# OpenScale.net
KiCad netlist of a schematic drawn in EAGLE
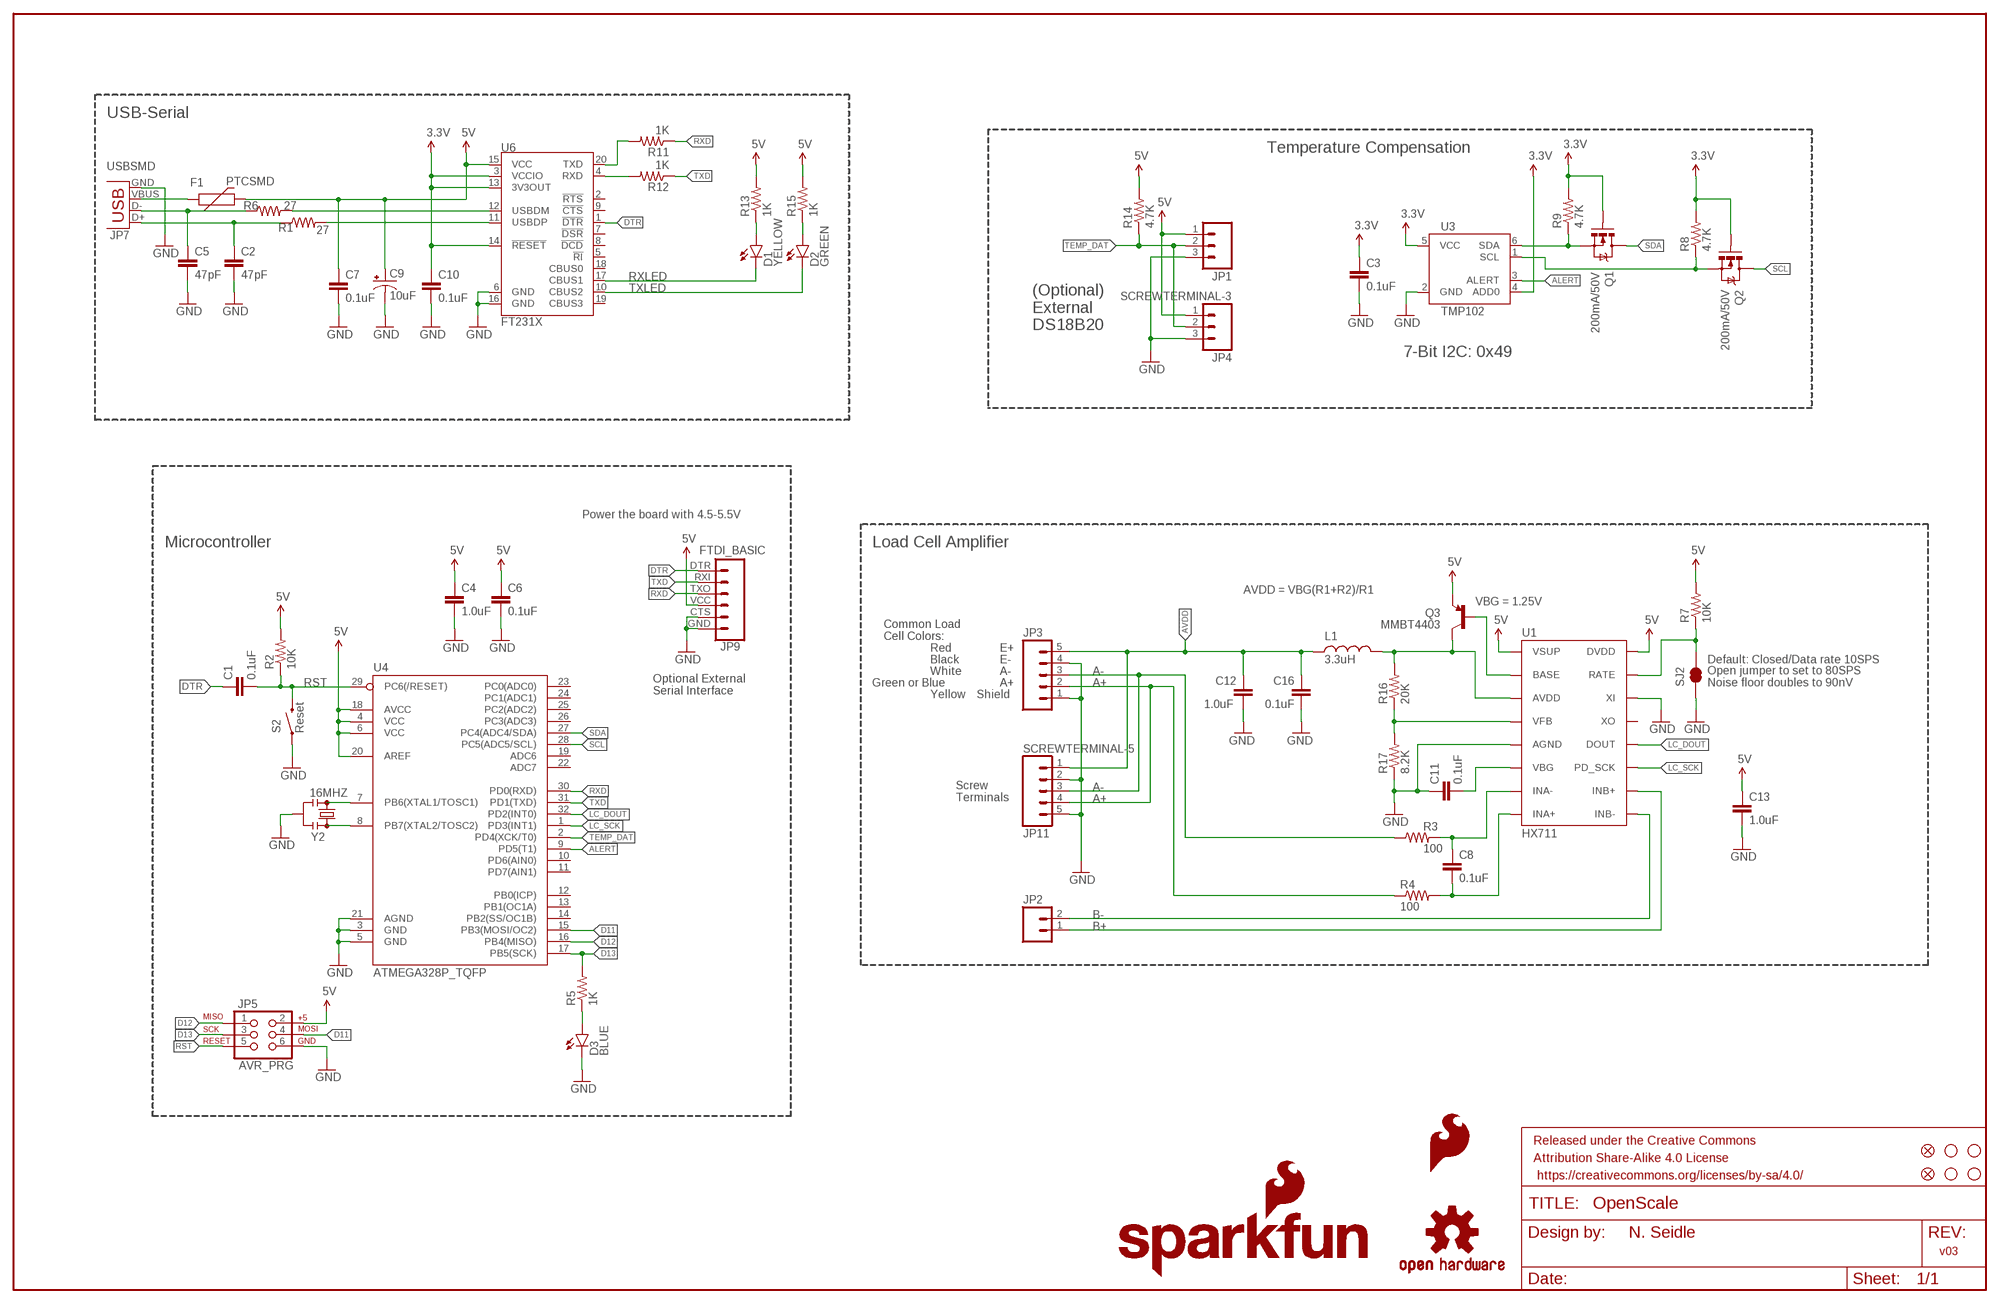
[diagram p0: schematic, sheet 1]

(export (version "E")
  (design (tool "Eeschema 10.0.6"))
  (components
    (comp (ref "C1")
      (value "0.1uF")
      (footprint "eagle-import:0603-CAP")
      (libsource (lib "eagle-import") (part "0.1UF-25V(+80/-20%)(0603)"))
    )
    (comp (ref "C2")
      (value "47pF")
      (footprint "eagle-import:0603-CAP")
      (libsource (lib "eagle-import") (part "47PF-50V-5%(0603)"))
    )
    (comp (ref "C3")
      (value "0.1uF")
      (footprint "eagle-import:0603-CAP")
      (libsource (lib "eagle-import") (part "0.1UF-25V(+80/-20%)(0603)"))
    )
    (comp (ref "C4")
      (value "1.0uF")
      (footprint "eagle-import:0603-CAP")
      (libsource (lib "eagle-import") (part "1.0UF-16V-10%(0603)"))
    )
    (comp (ref "C5")
      (value "47pF")
      (footprint "eagle-import:0603-CAP")
      (libsource (lib "eagle-import") (part "47PF-50V-5%(0603)"))
    )
    (comp (ref "C6")
      (value "0.1uF")
      (footprint "eagle-import:0603-CAP")
      (libsource (lib "eagle-import") (part "0.1UF-25V(+80/-20%)(0603)"))
    )
    (comp (ref "C7")
      (value "0.1uF")
      (footprint "eagle-import:0603-CAP")
      (libsource (lib "eagle-import") (part "0.1UF-25V(+80/-20%)(0603)"))
    )
    (comp (ref "C8")
      (value "0.1uF")
      (footprint "eagle-import:0603-CAP")
      (libsource (lib "eagle-import") (part "0.1UF-25V(+80/-20%)(0603)"))
    )
    (comp (ref "C9")
      (value "10uF")
      (footprint "eagle-import:EIA3216")
      (libsource (lib "eagle-import") (part "10UF-16V-10%(TANT)"))
    )
    (comp (ref "C10")
      (value "0.1uF")
      (footprint "eagle-import:0603-CAP")
      (libsource (lib "eagle-import") (part "0.1UF-25V(+80/-20%)(0603)"))
    )
    (comp (ref "C11")
      (value "0.1uF")
      (footprint "eagle-import:0603-CAP")
      (libsource (lib "eagle-import") (part "0.1UF-25V(+80/-20%)(0603)"))
    )
    (comp (ref "C12")
      (value "1.0uF")
      (footprint "eagle-import:0603-CAP")
      (libsource (lib "eagle-import") (part "1.0UF-16V-10%(0603)"))
    )
    (comp (ref "C13")
      (value "1.0uF")
      (footprint "eagle-import:0603-CAP")
      (libsource (lib "eagle-import") (part "1.0UF-16V-10%(0603)"))
    )
    (comp (ref "C16")
      (value "0.1uF")
      (footprint "eagle-import:0603-CAP")
      (libsource (lib "eagle-import") (part "0.1UF-25V(+80/-20%)(0603)"))
    )
    (comp (ref "D1")
      (value "YELLOW")
      (footprint "eagle-import:LED-1206")
      (libsource (lib "eagle-import") (part "LED-YELLOWLARGE"))
    )
    (comp (ref "D2")
      (value "GREEN")
      (footprint "eagle-import:LED-1206")
      (libsource (lib "eagle-import") (part "LED-GREENLARGE"))
    )
    (comp (ref "D3")
      (value "BLUE")
      (footprint "eagle-import:LED-1206")
      (libsource (lib "eagle-import") (part "LED-BLUE1206"))
    )
    (comp (ref "F1")
      (value "PTCSMD")
      (footprint "eagle-import:PTC-1206")
      (libsource (lib "eagle-import") (part "PTCSMD"))
    )
    (comp (ref "FID1")
      (value "FIDUCIAL1X2")
      (footprint "eagle-import:FIDUCIAL-1X2")
      (libsource (lib "eagle-import") (part "FIDUCIAL1X2"))
    )
    (comp (ref "FID2")
      (value "FIDUCIAL1X2")
      (footprint "eagle-import:FIDUCIAL-1X2")
      (libsource (lib "eagle-import") (part "FIDUCIAL1X2"))
    )
    (comp (ref "FRAME1")
      (value "FRAME-LEDGER")
      (footprint "eagle-import:CREATIVE_COMMONS")
      (fields (field (name "DESIGNER") "N. Seidle") (field (name "VERSION") "v02"))
      (libsource (lib "eagle-import") (part "FRAME-LEDGER"))
    )
    (comp (ref "JP1")
      (value "M031X03_NO_SILK")
      (footprint "eagle-import:1X03_NO_SILK")
      (libsource (lib "eagle-import") (part "M031X03_NO_SILK"))
    )
    (comp (ref "JP2")
      (value "M02PTH")
      (footprint "eagle-import:1X02")
      (libsource (lib "eagle-import") (part "M02PTH"))
    )
    (comp (ref "JP3")
      (value "M05NO_SILK")
      (footprint "eagle-import:1X05_NO_SILK")
      (libsource (lib "eagle-import") (part "M05NO_SILK"))
    )
    (comp (ref "JP4")
      (value "SCREWTERMINAL-3")
      (footprint "eagle-import:SCREWTERMINAL-3.5MM-3_LOCK.007S")
      (libsource (lib "eagle-import") (part "M03SCREW_LOCK"))
    )
    (comp (ref "JP5")
      (value "AVR_PRG")
      (footprint "eagle-import:2X3")
      (libsource (lib "eagle-import") (part "AVR_SPI_PRG_6PTH"))
    )
    (comp (ref "JP7")
      (value "USBSMD")
      (footprint "eagle-import:USB-MINIB")
      (libsource (lib "eagle-import") (part "USBSMD"))
    )
    (comp (ref "JP9")
      (value "FTDI_BASIC")
      (footprint "eagle-import:FTDI_BASIC")
      (libsource (lib "eagle-import") (part "FTDI_BASICPTH"))
    )
    (comp (ref "JP11")
      (value "SCREWTERMINAL-5")
      (footprint "eagle-import:SCREWTERMINAL-3.5MM-5")
      (libsource (lib "eagle-import") (part "M05SCREW"))
    )
    (comp (ref "L1")
      (value "3.3uH")
      (footprint "eagle-import:0805")
      (libsource (lib "eagle-import") (part "INDUCTOR0805"))
    )
    (comp (ref "LOGO1")
      (value "SFE_LOGO_NAME_FLAME.1_INCH")
      (footprint "eagle-import:SFE_LOGO_NAME_FLAME_.1")
      (libsource (lib "eagle-import") (part "SFE_LOGO_NAME_FLAME.1_INCH"))
    )
    (comp (ref "LOGO2")
      (value "OSHW-LOGOS")
      (footprint "eagle-import:OSHW-LOGO-S")
      (libsource (lib "eagle-import") (part "OSHW-LOGOS"))
    )
    (comp (ref "LOGO3")
      (value "SFE_LOGO_FLAME.1_STOP")
      (footprint "eagle-import:SFE_LOGO_FLAME_STOP_.1")
      (libsource (lib "eagle-import") (part "SFE_LOGO_FLAME.1_STOP"))
    )
    (comp (ref "LOGO4")
      (value "SFE_LOGO_NAME_FLAME.1_INCH")
      (footprint "eagle-import:SFE_LOGO_NAME_FLAME_.1")
      (libsource (lib "eagle-import") (part "SFE_LOGO_NAME_FLAME.1_INCH"))
    )
    (comp (ref "Q1")
      (value "200mA/50V")
      (footprint "eagle-import:SOT23-3")
      (libsource (lib "eagle-import") (part "MOSFET-NCHANNELBSS138"))
    )
    (comp (ref "Q2")
      (value "200mA/50V")
      (footprint "eagle-import:SOT23-3")
      (libsource (lib "eagle-import") (part "MOSFET-NCHANNELBSS138"))
    )
    (comp (ref "Q3")
      (value "MMBT4403")
      (footprint "eagle-import:SOT23-3")
      (libsource (lib "eagle-import") (part "TRANSISTOR_PNPMMBT4403"))
    )
    (comp (ref "R1")
      (value "27")
      (footprint "eagle-import:0603")
      (libsource (lib "eagle-import") (part "27OHM1/10W1%(0603)"))
    )
    (comp (ref "R2")
      (value "10K")
      (footprint "eagle-import:0603-RES")
      (libsource (lib "eagle-import") (part "10KOHM-1/10W-1%(0603)0603"))
    )
    (comp (ref "R3")
      (value "100")
      (footprint "eagle-import:0603-RES")
      (libsource (lib "eagle-import") (part "100OHM-1/10W-1%(0603)"))
    )
    (comp (ref "R4")
      (value "100")
      (footprint "eagle-import:0603-RES")
      (libsource (lib "eagle-import") (part "100OHM-1/10W-1%(0603)"))
    )
    (comp (ref "R5")
      (value "1K")
      (footprint "eagle-import:0603-RES")
      (libsource (lib "eagle-import") (part "1KOHM-1/10W-1%(0603)"))
    )
    (comp (ref "R6")
      (value "27")
      (footprint "eagle-import:0603")
      (libsource (lib "eagle-import") (part "27OHM1/10W1%(0603)"))
    )
    (comp (ref "R7")
      (value "10K")
      (footprint "eagle-import:0603-RES")
      (libsource (lib "eagle-import") (part "10KOHM-1/10W-1%(0603)0603"))
    )
    (comp (ref "R8")
      (value "4.7K")
      (footprint "eagle-import:0603-RES")
      (libsource (lib "eagle-import") (part "4.7KOHM-1/10W-1%(0603)"))
    )
    (comp (ref "R9")
      (value "4.7K")
      (footprint "eagle-import:0603-RES")
      (libsource (lib "eagle-import") (part "4.7KOHM-1/10W-1%(0603)"))
    )
    (comp (ref "R11")
      (value "1K")
      (footprint "eagle-import:0603-RES")
      (libsource (lib "eagle-import") (part "1KOHM-1/10W-1%(0603)"))
    )
    (comp (ref "R12")
      (value "1K")
      (footprint "eagle-import:0603-RES")
      (libsource (lib "eagle-import") (part "1KOHM-1/10W-1%(0603)"))
    )
    (comp (ref "R13")
      (value "1K")
      (footprint "eagle-import:0603-RES")
      (libsource (lib "eagle-import") (part "1KOHM-1/10W-1%(0603)"))
    )
    (comp (ref "R14")
      (value "4.7K")
      (footprint "eagle-import:0603-RES")
      (libsource (lib "eagle-import") (part "4.7KOHM-1/10W-1%(0603)"))
    )
    (comp (ref "R15")
      (value "1K")
      (footprint "eagle-import:0603-RES")
      (libsource (lib "eagle-import") (part "1KOHM-1/10W-1%(0603)"))
    )
    (comp (ref "R16")
      (value "20K")
      (footprint "eagle-import:0603-RES")
      (libsource (lib "eagle-import") (part "20KOHM1/10W1%(0603)"))
    )
    (comp (ref "R17")
      (value "8.2K")
      (footprint "eagle-import:0603-RES")
      (libsource (lib "eagle-import") (part "8.2KOHM-1/10W-5%(0603)"))
    )
    (comp (ref "S2")
      (value "Reset")
      (footprint "eagle-import:TACTILE-SWITCH-1101NE")
      (libsource (lib "eagle-import") (part "SWITCH-MOMENTARY-2SMD-1101NE"))
    )
    (comp (ref "SJ2")
      (value "JUMPER-PAD-2-NC_BY_TRACE")
      (footprint "eagle-import:PAD-JUMPER-2-NC_BY_TRACE_YES_SILK")
      (libsource (lib "eagle-import") (part "JUMPER-PAD-2-NC_BY_TRACE"))
    )
    (comp (ref "STANDOFF1")
      (value "STAND-OFF")
      (footprint "eagle-import:STAND-OFF")
      (libsource (lib "eagle-import") (part "STAND-OFF"))
    )
    (comp (ref "STANDOFF2")
      (value "STAND-OFF")
      (footprint "eagle-import:STAND-OFF")
      (libsource (lib "eagle-import") (part "STAND-OFF"))
    )
    (comp (ref "STANDOFF3")
      (value "STAND-OFF")
      (footprint "eagle-import:STAND-OFF")
      (libsource (lib "eagle-import") (part "STAND-OFF"))
    )
    (comp (ref "STANDOFF4")
      (value "STAND-OFF")
      (footprint "eagle-import:STAND-OFF")
      (libsource (lib "eagle-import") (part "STAND-OFF"))
    )
    (comp (ref "U1")
      (value "HX711")
      (footprint "eagle-import:SO16")
      (libsource (lib "eagle-import") (part "HX711HX711"))
    )
    (comp (ref "U3")
      (value "TMP102")
      (footprint "eagle-import:SOT563")
      (libsource (lib "eagle-import") (part "TMP102"))
    )
    (comp (ref "U4")
      (value "ATMEGA328P_TQFP")
      (footprint "eagle-import:TQFP32-08")
      (libsource (lib "eagle-import") (part "ATMEGA328P_TQFP"))
    )
    (comp (ref "U6")
      (value "FT231X")
      (footprint "eagle-import:SSOP20_L")
      (libsource (lib "eagle-import") (part "FT231XS"))
    )
    (comp (ref "Y2")
      (value "16MHZ")
      (footprint "eagle-import:RESONATOR-SMD")
      (libsource (lib "eagle-import") (part "RESONATOR16MHZ"))
    )
  )
  (nets
    (net (code "1") (name "/A+") (class "Default")
      (node (ref "JP11") (pin "4") (pinfunction "4_4") (pintype "passive"))
      (node (ref "JP3") (pin "2") (pinfunction "2_2") (pintype "passive"))
      (node (ref "R4") (pin "1") (pinfunction "1_1") (pintype "passive"))
    )
    (net (code "2") (name "/A-") (class "Default")
      (node (ref "JP11") (pin "3") (pinfunction "3_3") (pintype "passive"))
      (node (ref "JP3") (pin "3") (pinfunction "3_3") (pintype "passive"))
      (node (ref "R3") (pin "1") (pinfunction "1_1") (pintype "passive"))
    )
    (net (code "3") (name "/B+") (class "Default")
      (node (ref "JP2") (pin "1") (pinfunction "1_1") (pintype "passive"))
      (node (ref "U1") (pin "10") (pinfunction "INB+_10") (pintype "bidirectional"))
    )
    (net (code "4") (name "/B-") (class "Default")
      (node (ref "JP2") (pin "2") (pinfunction "2_2") (pintype "passive"))
      (node (ref "U1") (pin "9") (pinfunction "INB-_9") (pintype "bidirectional"))
    )
    (net (code "5") (name "/RXLED") (class "Default")
      (node (ref "D1") (pin "C") (pinfunction "C_C") (pintype "passive"))
      (node (ref "U6") (pin "17") (pinfunction "CBUS1_17") (pintype "bidirectional"))
    )
    (net (code "6") (name "/TXLED") (class "Default")
      (node (ref "D2") (pin "C") (pinfunction "C_C") (pintype "passive"))
      (node (ref "U6") (pin "10") (pinfunction "CBUS2_10") (pintype "bidirectional"))
    )
    (net (code "7") (name "3.3V") (class "Default")
      (node (ref "C10") (pin "1") (pinfunction "1_1") (pintype "passive"))
      (node (ref "C3") (pin "1") (pinfunction "1_1") (pintype "passive"))
      (node (ref "Q1") (pin "1") (pinfunction "G_1") (pintype "passive"))
      (node (ref "Q2") (pin "1") (pinfunction "G_1") (pintype "passive"))
      (node (ref "R8") (pin "2") (pinfunction "2_2") (pintype "passive"))
      (node (ref "R9") (pin "2") (pinfunction "2_2") (pintype "passive"))
      (node (ref "U3") (pin "4") (pinfunction "ADD0_4") (pintype "bidirectional"))
      (node (ref "U3") (pin "5") (pinfunction "VCC_5") (pintype "bidirectional"))
      (node (ref "U6") (pin "13") (pinfunction "3V3OUT_13") (pintype "bidirectional"))
      (node (ref "U6") (pin "14") (pinfunction "~{RESET}_14") (pintype "bidirectional"))
      (node (ref "U6") (pin "3") (pinfunction "VCCIO_3") (pintype "bidirectional"))
    )
    (net (code "8") (name "5V") (class "Default")
      (node (ref "C13") (pin "1") (pinfunction "1_1") (pintype "passive"))
      (node (ref "C4") (pin "1") (pinfunction "1_1") (pintype "passive"))
      (node (ref "C6") (pin "1") (pinfunction "1_1") (pintype "passive"))
      (node (ref "C7") (pin "1") (pinfunction "1_1") (pintype "passive"))
      (node (ref "C9") (pin "A") (pinfunction "+_A") (pintype "passive"))
      (node (ref "F1") (pin "2") (pinfunction "2_2") (pintype "bidirectional"))
      (node (ref "JP1") (pin "1") (pinfunction "1_1") (pintype "passive"))
      (node (ref "JP4") (pin "1") (pinfunction "1_1") (pintype "passive"))
      (node (ref "JP5") (pin "2") (pinfunction "2_2") (pintype "passive"))
      (node (ref "JP9") (pin "VCC") (pinfunction "4_VCC") (pintype "passive"))
      (node (ref "Q3") (pin "2") (pinfunction "E_2") (pintype "passive"))
      (node (ref "R13") (pin "2") (pinfunction "2_2") (pintype "passive"))
      (node (ref "R14") (pin "2") (pinfunction "2_2") (pintype "passive"))
      (node (ref "R15") (pin "2") (pinfunction "2_2") (pintype "passive"))
      (node (ref "R2") (pin "2") (pinfunction "2_2") (pintype "passive"))
      (node (ref "R7") (pin "2") (pinfunction "2_2") (pintype "passive"))
      (node (ref "U1") (pin "1") (pinfunction "VSUP_1") (pintype "bidirectional"))
      (node (ref "U1") (pin "16") (pinfunction "DVDD_16") (pintype "bidirectional"))
      (node (ref "U4") (pin "18") (pinfunction "AVCC_18") (pintype "bidirectional"))
      (node (ref "U4") (pin "20") (pinfunction "AREF_20") (pintype "bidirectional"))
      (node (ref "U4") (pin "4") (pinfunction "VCC_4") (pintype "bidirectional"))
      (node (ref "U4") (pin "6") (pinfunction "VCC_6") (pintype "bidirectional"))
      (node (ref "U6") (pin "15") (pinfunction "VCC_15") (pintype "bidirectional"))
    )
    (net (code "9") (name "ALERT") (class "Default")
      (node (ref "U3") (pin "3") (pinfunction "ALERT_3") (pintype "bidirectional"))
      (node (ref "U4") (pin "9") (pinfunction "PD5(T1)_9") (pintype "bidirectional"))
    )
    (net (code "10") (name "AVDD") (class "Default")
      (node (ref "C12") (pin "2") (pinfunction "2_2") (pintype "passive"))
      (node (ref "C16") (pin "1") (pinfunction "1_1") (pintype "passive"))
      (node (ref "JP11") (pin "1") (pinfunction "1_1") (pintype "passive"))
      (node (ref "JP3") (pin "5") (pinfunction "5_5") (pintype "passive"))
      (node (ref "L1") (pin "1") (pinfunction "1_1") (pintype "passive"))
    )
    (net (code "11") (name "D11") (class "Default")
      (node (ref "JP5") (pin "4") (pinfunction "4_4") (pintype "passive"))
      (node (ref "U4") (pin "15") (pinfunction "PB3(MOSI/OC2)_15") (pintype "bidirectional"))
    )
    (net (code "12") (name "D12") (class "Default")
      (node (ref "JP5") (pin "1") (pinfunction "1_1") (pintype "passive"))
      (node (ref "U4") (pin "16") (pinfunction "PB4(MISO)_16") (pintype "bidirectional"))
    )
    (net (code "13") (name "D13") (class "Default")
      (node (ref "JP5") (pin "3") (pinfunction "3_3") (pintype "passive"))
      (node (ref "R5") (pin "2") (pinfunction "2_2") (pintype "passive"))
      (node (ref "U4") (pin "17") (pinfunction "PB5(SCK)_17") (pintype "bidirectional"))
    )
    (net (code "14") (name "DTR") (class "Default")
      (node (ref "C1") (pin "1") (pinfunction "1_1") (pintype "passive"))
      (node (ref "JP9") (pin "DTR") (pinfunction "1_DTR") (pintype "passive"))
      (node (ref "U6") (pin "1") (pinfunction "~{DTR}_1") (pintype "bidirectional"))
    )
    (net (code "15") (name "GND") (class "Default")
      (node (ref "C10") (pin "2") (pinfunction "2_2") (pintype "passive"))
      (node (ref "C11") (pin "1") (pinfunction "1_1") (pintype "passive"))
      (node (ref "C12") (pin "1") (pinfunction "1_1") (pintype "passive"))
      (node (ref "C13") (pin "2") (pinfunction "2_2") (pintype "passive"))
      (node (ref "C16") (pin "2") (pinfunction "2_2") (pintype "passive"))
      (node (ref "C2") (pin "2") (pinfunction "2_2") (pintype "passive"))
      (node (ref "C3") (pin "2") (pinfunction "2_2") (pintype "passive"))
      (node (ref "C4") (pin "2") (pinfunction "2_2") (pintype "passive"))
      (node (ref "C5") (pin "2") (pinfunction "2_2") (pintype "passive"))
      (node (ref "C6") (pin "2") (pinfunction "2_2") (pintype "passive"))
      (node (ref "C7") (pin "2") (pinfunction "2_2") (pintype "passive"))
      (node (ref "C9") (pin "C") (pinfunction "-_C") (pintype "passive"))
      (node (ref "D3") (pin "C") (pinfunction "C_C") (pintype "passive"))
      (node (ref "JP1") (pin "3") (pinfunction "3_3") (pintype "passive"))
      (node (ref "JP11") (pin "2") (pinfunction "2_2") (pintype "passive"))
      (node (ref "JP11") (pin "5") (pinfunction "5_5") (pintype "passive"))
      (node (ref "JP3") (pin "1") (pinfunction "1_1") (pintype "passive"))
      (node (ref "JP3") (pin "4") (pinfunction "4_4") (pintype "passive"))
      (node (ref "JP4") (pin "3") (pinfunction "3_3") (pintype "passive"))
      (node (ref "JP5") (pin "6") (pinfunction "6_6") (pintype "passive"))
      (node (ref "JP7") (pin "GND") (pinfunction "GND_GND") (pintype "bidirectional"))
      (node (ref "JP9") (pin "CTS") (pinfunction "5_CTS") (pintype "passive"))
      (node (ref "JP9") (pin "GND") (pinfunction "6_GND") (pintype "passive"))
      (node (ref "R17") (pin "1") (pinfunction "1_1") (pintype "passive"))
      (node (ref "S2") (pin "1") (pinfunction "1_1") (pintype "passive"))
      (node (ref "SJ2") (pin "1") (pinfunction "1_1") (pintype "passive"))
      (node (ref "U1") (pin "14") (pinfunction "XI_14") (pintype "bidirectional"))
      (node (ref "U1") (pin "5") (pinfunction "AGND_5") (pintype "bidirectional"))
      (node (ref "U3") (pin "2") (pinfunction "GND_2") (pintype "bidirectional"))
      (node (ref "U4") (pin "21") (pinfunction "AGND_21") (pintype "bidirectional"))
      (node (ref "U4") (pin "3") (pinfunction "GND_3") (pintype "bidirectional"))
      (node (ref "U4") (pin "5") (pinfunction "GND_5") (pintype "bidirectional"))
      (node (ref "U6") (pin "16") (pinfunction "GND_16") (pintype "bidirectional"))
      (node (ref "U6") (pin "6") (pinfunction "GND_6") (pintype "bidirectional"))
      (node (ref "Y2") (pin "2") (pinfunction "2_2") (pintype "passive"))
    )
    (net (code "16") (name "LC_DOUT") (class "Default")
      (node (ref "U1") (pin "12") (pinfunction "DOUT_12") (pintype "bidirectional"))
      (node (ref "U4") (pin "32") (pinfunction "PD2(INT0)_32") (pintype "bidirectional"))
    )
    (net (code "17") (name "LC_SCK") (class "Default")
      (node (ref "U1") (pin "11") (pinfunction "PD_SCK_11") (pintype "bidirectional"))
      (node (ref "U4") (pin "1") (pinfunction "PD3(INT1)_1") (pintype "bidirectional"))
    )
    (net (code "18") (name "Net-(C2-Pad1)") (class "Default")
      (node (ref "C2") (pin "1") (pinfunction "1_1") (pintype "passive"))
      (node (ref "JP7") (pin "D+") (pinfunction "D+_D+") (pintype "bidirectional"))
      (node (ref "R1") (pin "1") (pinfunction "1_1") (pintype "passive"))
    )
    (net (code "19") (name "Net-(C5-Pad1)") (class "Default")
      (node (ref "C5") (pin "1") (pinfunction "1_1") (pintype "passive"))
      (node (ref "JP7") (pin "D-") (pinfunction "D-_D-") (pintype "bidirectional"))
      (node (ref "R6") (pin "1") (pinfunction "1_1") (pintype "passive"))
    )
    (net (code "20") (name "Net-(D1-PadA)") (class "Default")
      (node (ref "D1") (pin "A") (pinfunction "A_A") (pintype "passive"))
      (node (ref "R13") (pin "1") (pinfunction "1_1") (pintype "passive"))
    )
    (net (code "21") (name "Net-(D2-PadA)") (class "Default")
      (node (ref "D2") (pin "A") (pinfunction "A_A") (pintype "passive"))
      (node (ref "R15") (pin "1") (pinfunction "1_1") (pintype "passive"))
    )
    (net (code "22") (name "Net-(D3-PadA)") (class "Default")
      (node (ref "D3") (pin "A") (pinfunction "A_A") (pintype "passive"))
      (node (ref "R5") (pin "1") (pinfunction "1_1") (pintype "passive"))
    )
    (net (code "23") (name "Net-(F1-Pad1)") (class "Default")
      (node (ref "F1") (pin "1") (pinfunction "1_1") (pintype "bidirectional"))
      (node (ref "JP7") (pin "VBUS") (pinfunction "VBUS_VBUS") (pintype "bidirectional"))
    )
    (net (code "24") (name "Net-(Q1-S)") (class "Default")
      (node (ref "Q1") (pin "2") (pinfunction "S_2") (pintype "passive"))
      (node (ref "R9") (pin "1") (pinfunction "1_1") (pintype "passive"))
      (node (ref "U3") (pin "6") (pinfunction "SDA_6") (pintype "bidirectional"))
    )
    (net (code "25") (name "Net-(Q2-S)") (class "Default")
      (node (ref "Q2") (pin "2") (pinfunction "S_2") (pintype "passive"))
      (node (ref "R8") (pin "1") (pinfunction "1_1") (pintype "passive"))
      (node (ref "U3") (pin "1") (pinfunction "SCL_1") (pintype "bidirectional"))
    )
    (net (code "26") (name "Net-(Q3-B)") (class "Default")
      (node (ref "Q3") (pin "1") (pinfunction "B_1") (pintype "passive"))
      (node (ref "U1") (pin "2") (pinfunction "BASE_2") (pintype "bidirectional"))
    )
    (net (code "27") (name "Net-(Q3-C)") (class "Default")
      (node (ref "L1") (pin "2") (pinfunction "2_2") (pintype "passive"))
      (node (ref "Q3") (pin "3") (pinfunction "C_3") (pintype "passive"))
      (node (ref "R16") (pin "2") (pinfunction "2_2") (pintype "passive"))
      (node (ref "U1") (pin "3") (pinfunction "AVDD_3") (pintype "bidirectional"))
    )
    (net (code "28") (name "Net-(U1-INA+)") (class "Default")
      (node (ref "C8") (pin "2") (pinfunction "2_2") (pintype "passive"))
      (node (ref "R4") (pin "2") (pinfunction "2_2") (pintype "passive"))
      (node (ref "U1") (pin "8") (pinfunction "INA+_8") (pintype "bidirectional"))
    )
    (net (code "29") (name "Net-(U1-INA-)") (class "Default")
      (node (ref "C8") (pin "1") (pinfunction "1_1") (pintype "passive"))
      (node (ref "R3") (pin "2") (pinfunction "2_2") (pintype "passive"))
      (node (ref "U1") (pin "7") (pinfunction "INA-_7") (pintype "bidirectional"))
    )
    (net (code "30") (name "Net-(U1-RATE)") (class "Default")
      (node (ref "R7") (pin "1") (pinfunction "1_1") (pintype "passive"))
      (node (ref "SJ2") (pin "2") (pinfunction "2_2") (pintype "passive"))
      (node (ref "U1") (pin "15") (pinfunction "RATE_15") (pintype "bidirectional"))
    )
    (net (code "31") (name "Net-(U1-VBG)") (class "Default")
      (node (ref "C11") (pin "2") (pinfunction "2_2") (pintype "passive"))
      (node (ref "U1") (pin "6") (pinfunction "VBG_6") (pintype "bidirectional"))
    )
    (net (code "32") (name "Net-(U1-VFB)") (class "Default")
      (node (ref "R16") (pin "1") (pinfunction "1_1") (pintype "passive"))
      (node (ref "R17") (pin "2") (pinfunction "2_2") (pintype "passive"))
      (node (ref "U1") (pin "4") (pinfunction "VFB_4") (pintype "bidirectional"))
    )
    (net (code "33") (name "Net-(U4-PB6(XTAL1{slash}TOSC1))") (class "Default")
      (node (ref "U4") (pin "7") (pinfunction "PB6(XTAL1/TOSC1)_7") (pintype "bidirectional"))
      (node (ref "Y2") (pin "1") (pinfunction "1_1") (pintype "passive"))
    )
    (net (code "34") (name "Net-(U4-PB7(XTAL2{slash}TOSC2))") (class "Default")
      (node (ref "U4") (pin "8") (pinfunction "PB7(XTAL2/TOSC2)_8") (pintype "bidirectional"))
      (node (ref "Y2") (pin "3") (pinfunction "3_3") (pintype "passive"))
    )
    (net (code "35") (name "Net-(U6-RXD)") (class "Default")
      (node (ref "R12") (pin "2") (pinfunction "2_2") (pintype "passive"))
      (node (ref "U6") (pin "4") (pinfunction "RXD_4") (pintype "bidirectional"))
    )
    (net (code "36") (name "Net-(U6-TXD)") (class "Default")
      (node (ref "R11") (pin "2") (pinfunction "2_2") (pintype "passive"))
      (node (ref "U6") (pin "20") (pinfunction "TXD_20") (pintype "bidirectional"))
    )
    (net (code "37") (name "Net-(U6-USBDM)") (class "Default")
      (node (ref "R6") (pin "2") (pinfunction "2_2") (pintype "passive"))
      (node (ref "U6") (pin "12") (pinfunction "USBDM_12") (pintype "bidirectional"))
    )
    (net (code "38") (name "Net-(U6-USBDP)") (class "Default")
      (node (ref "R1") (pin "2") (pinfunction "2_2") (pintype "passive"))
      (node (ref "U6") (pin "11") (pinfunction "USBDP_11") (pintype "bidirectional"))
    )
    (net (code "39") (name "RST") (class "Default")
      (node (ref "C1") (pin "2") (pinfunction "2_2") (pintype "passive"))
      (node (ref "JP5") (pin "5") (pinfunction "5_5") (pintype "passive"))
      (node (ref "R2") (pin "1") (pinfunction "1_1") (pintype "passive"))
      (node (ref "S2") (pin "2") (pinfunction "2_2") (pintype "passive"))
      (node (ref "U4") (pin "29") (pinfunction "PC6(/RESET)_29") (pintype "bidirectional"))
    )
    (net (code "40") (name "RXD") (class "Default")
      (node (ref "JP9") (pin "TXO") (pinfunction "3_TXO") (pintype "passive"))
      (node (ref "R11") (pin "1") (pinfunction "1_1") (pintype "passive"))
      (node (ref "U4") (pin "30") (pinfunction "PD0(RXD)_30") (pintype "bidirectional"))
    )
    (net (code "41") (name "SCL") (class "Default")
      (node (ref "Q2") (pin "3") (pinfunction "D_3") (pintype "passive"))
      (node (ref "U4") (pin "28") (pinfunction "PC5(ADC5/SCL)_28") (pintype "bidirectional"))
    )
    (net (code "42") (name "SDA") (class "Default")
      (node (ref "Q1") (pin "3") (pinfunction "D_3") (pintype "passive"))
      (node (ref "U4") (pin "27") (pinfunction "PC4(ADC4/SDA)_27") (pintype "bidirectional"))
    )
    (net (code "43") (name "TEMP_DAT") (class "Default")
      (node (ref "JP1") (pin "2") (pinfunction "2_2") (pintype "passive"))
      (node (ref "JP4") (pin "2") (pinfunction "2_2") (pintype "passive"))
      (node (ref "R14") (pin "1") (pinfunction "1_1") (pintype "passive"))
      (node (ref "U4") (pin "2") (pinfunction "PD4(XCK/T0)_2") (pintype "bidirectional"))
    )
    (net (code "44") (name "TXD") (class "Default")
      (node (ref "JP9") (pin "RXI") (pinfunction "2_RXI") (pintype "passive"))
      (node (ref "R12") (pin "1") (pinfunction "1_1") (pintype "passive"))
      (node (ref "U4") (pin "31") (pinfunction "PD1(TXD)_31") (pintype "bidirectional"))
    )
    (net (code "45") (name "unconnected-(U1-XO-Pad13)") (class "Default")
      (node (ref "U1") (pin "13") (pinfunction "XO_13") (pintype "bidirectional"))
    )
    (net (code "46") (name "unconnected-(U4-ADC6-Pad19)") (class "Default")
      (node (ref "U4") (pin "19") (pinfunction "ADC6_19") (pintype "bidirectional"))
    )
    (net (code "47") (name "unconnected-(U4-ADC7-Pad22)") (class "Default")
      (node (ref "U4") (pin "22") (pinfunction "ADC7_22") (pintype "bidirectional"))
    )
    (net (code "48") (name "unconnected-(U4-PB0(ICP)-Pad12)") (class "Default")
      (node (ref "U4") (pin "12") (pinfunction "PB0(ICP)_12") (pintype "bidirectional"))
    )
    (net (code "49") (name "unconnected-(U4-PB1(OC1A)-Pad13)") (class "Default")
      (node (ref "U4") (pin "13") (pinfunction "PB1(OC1A)_13") (pintype "bidirectional"))
    )
    (net (code "50") (name "unconnected-(U4-PB2(SS{slash}OC1B)-Pad14)") (class "Default")
      (node (ref "U4") (pin "14") (pinfunction "PB2(SS/OC1B)_14") (pintype "bidirectional"))
    )
    (net (code "51") (name "unconnected-(U4-PC0(ADC0)-Pad23)") (class "Default")
      (node (ref "U4") (pin "23") (pinfunction "PC0(ADC0)_23") (pintype "bidirectional"))
    )
    (net (code "52") (name "unconnected-(U4-PC1(ADC1)-Pad24)") (class "Default")
      (node (ref "U4") (pin "24") (pinfunction "PC1(ADC1)_24") (pintype "bidirectional"))
    )
    (net (code "53") (name "unconnected-(U4-PC2(ADC2)-Pad25)") (class "Default")
      (node (ref "U4") (pin "25") (pinfunction "PC2(ADC2)_25") (pintype "bidirectional"))
    )
    (net (code "54") (name "unconnected-(U4-PC3(ADC3)-Pad26)") (class "Default")
      (node (ref "U4") (pin "26") (pinfunction "PC3(ADC3)_26") (pintype "bidirectional"))
    )
    (net (code "55") (name "unconnected-(U4-PD6(AIN0)-Pad10)") (class "Default")
      (node (ref "U4") (pin "10") (pinfunction "PD6(AIN0)_10") (pintype "bidirectional"))
    )
    (net (code "56") (name "unconnected-(U4-PD7(AIN1)-Pad11)") (class "Default")
      (node (ref "U4") (pin "11") (pinfunction "PD7(AIN1)_11") (pintype "bidirectional"))
    )
    (net (code "57") (name "unconnected-(U6-CBUS0-Pad18)") (class "Default")
      (node (ref "U6") (pin "18") (pinfunction "CBUS0_18") (pintype "bidirectional"))
    )
    (net (code "58") (name "unconnected-(U6-CBUS3-Pad19)") (class "Default")
      (node (ref "U6") (pin "19") (pinfunction "CBUS3_19") (pintype "bidirectional"))
    )
    (net (code "59") (name "unconnected-(U6-~{CTS}-Pad9)") (class "Default")
      (node (ref "U6") (pin "9") (pinfunction "~{CTS}_9") (pintype "bidirectional"))
    )
    (net (code "60") (name "unconnected-(U6-~{DCD}-Pad8)") (class "Default")
      (node (ref "U6") (pin "8") (pinfunction "~{DCD}_8") (pintype "bidirectional"))
    )
    (net (code "61") (name "unconnected-(U6-~{DSR}-Pad7)") (class "Default")
      (node (ref "U6") (pin "7") (pinfunction "~{DSR}_7") (pintype "bidirectional"))
    )
    (net (code "62") (name "unconnected-(U6-~{RI}-Pad5)") (class "Default")
      (node (ref "U6") (pin "5") (pinfunction "~{RI}_5") (pintype "bidirectional"))
    )
    (net (code "63") (name "unconnected-(U6-~{RTS}-Pad2)") (class "Default")
      (node (ref "U6") (pin "2") (pinfunction "~{RTS}_2") (pintype "bidirectional"))
    )
  )
)
